# DDR4_Interface.net
KiCad netlist of a schematic drawn in Altium Designer
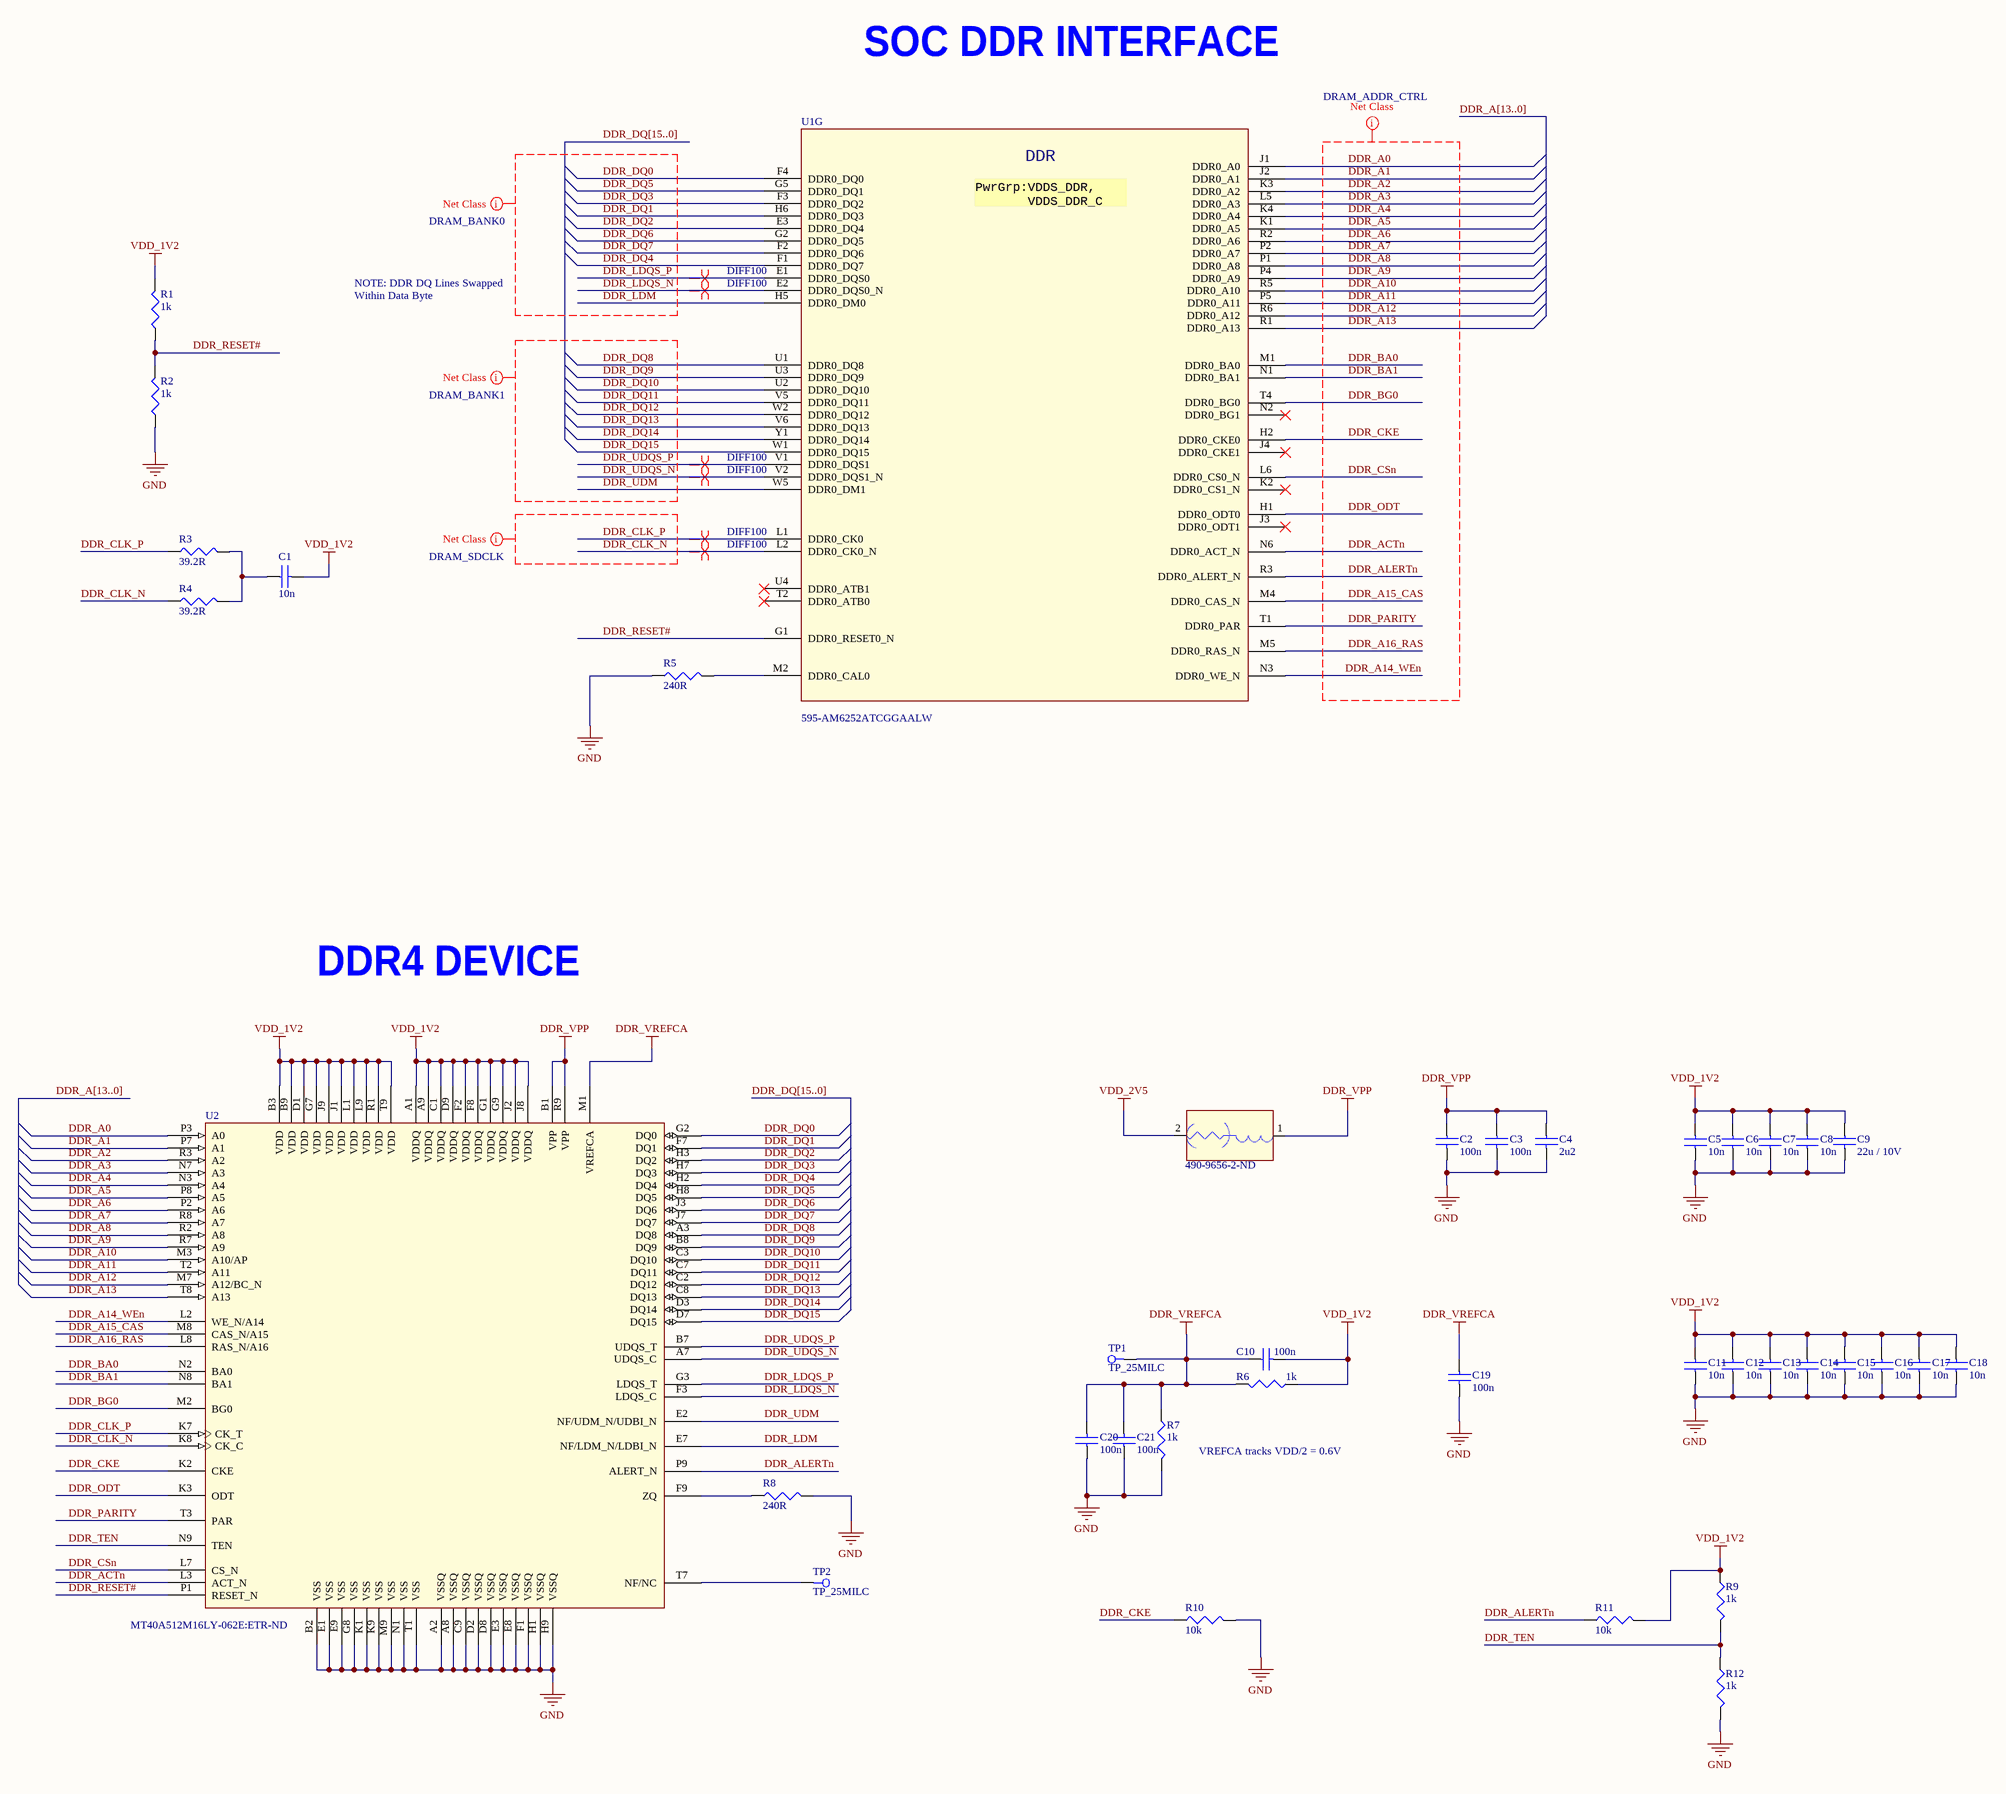
[diagram p0: DDR4 Interface.SchDoc]

(export (version "E")
  (design (tool "Eeschema 10.0.6"))
  (components
    (comp (ref "C1")
      (value "10n")
      (footprint "C0201")
      (description "CAP CER .01UF 16V 10% X5R 0201")
      (fields
        (field (name "MANUFACTURER") "TDK Corporation")
        (field (name "MANUFACTURER PART NUMBER") "C0603X5R1C103K030BA")
        (field (name ".CREATOR") "MM")
        (field (name ".CHECKED PCB") "MM")
        (field (name ".CHECKED SCH") "MM")
      )
      (libsource (lib "Schlib AM625") (part "C0603X5R1C103K030BA"))
    )
    (comp (ref "C2")
      (value "100n")
      (footprint "C0201")
      (description "CAP CER 0.1UF 16V 10% X5R 0201")
      (fields
        (field (name "MANUFACTURER") "TDK Corporation")
        (field (name "MANUFACTURER PART NUMBER") "C0603X5R1C104K030BC")
        (field (name ".CREATOR") "MM")
        (field (name ".CHECKED PCB") "MM")
        (field (name ".CHECKED SCH") "MM")
      )
      (libsource (lib "Schlib AM625") (part "C0603X5R1C104K030BC"))
    )
    (comp (ref "C3")
      (value "100n")
      (footprint "C0201")
      (description "CAP CER 0.1UF 16V 10% X5R 0201")
      (fields
        (field (name "MANUFACTURER") "TDK Corporation")
        (field (name "MANUFACTURER PART NUMBER") "C0603X5R1C104K030BC")
        (field (name ".CREATOR") "MM")
        (field (name ".CHECKED PCB") "MM")
        (field (name ".CHECKED SCH") "MM")
      )
      (libsource (lib "Schlib AM625") (part "C0603X5R1C104K030BC"))
    )
    (comp (ref "C4")
      (value "2u2")
      (footprint "C0402")
      (description "CAP CER 2.2UF 10V 10% X5R 0402")
      (fields
        (field (name "MANUFACTURER") "TDK Corporation")
        (field (name "MANUFACTURER PART NUMBER") "C1005X5R1A225K")
      )
      (libsource (lib "Schlib AM625") (part "C1005X5R1A225K"))
    )
    (comp (ref "C5")
      (value "10n")
      (footprint "C0201")
      (description "CAP CER .01UF 16V 10% X5R 0201")
      (fields
        (field (name "MANUFACTURER") "TDK Corporation")
        (field (name "MANUFACTURER PART NUMBER") "C0603X5R1C103K030BA")
        (field (name ".CREATOR") "MM")
        (field (name ".CHECKED PCB") "MM")
        (field (name ".CHECKED SCH") "MM")
      )
      (libsource (lib "Schlib AM625") (part "C0603X5R1C103K030BA"))
    )
    (comp (ref "C6")
      (value "10n")
      (footprint "C0201")
      (description "CAP CER .01UF 16V 10% X5R 0201")
      (fields
        (field (name "MANUFACTURER") "TDK Corporation")
        (field (name "MANUFACTURER PART NUMBER") "C0603X5R1C103K030BA")
        (field (name ".CREATOR") "MM")
        (field (name ".CHECKED PCB") "MM")
        (field (name ".CHECKED SCH") "MM")
      )
      (libsource (lib "Schlib AM625") (part "C0603X5R1C103K030BA"))
    )
    (comp (ref "C7")
      (value "10n")
      (footprint "C0201")
      (description "CAP CER .01UF 16V 10% X5R 0201")
      (fields
        (field (name "MANUFACTURER") "TDK Corporation")
        (field (name "MANUFACTURER PART NUMBER") "C0603X5R1C103K030BA")
        (field (name ".CREATOR") "MM")
        (field (name ".CHECKED PCB") "MM")
        (field (name ".CHECKED SCH") "MM")
      )
      (libsource (lib "Schlib AM625") (part "C0603X5R1C103K030BA"))
    )
    (comp (ref "C8")
      (value "10n")
      (footprint "C0201")
      (description "CAP CER .01UF 16V 10% X5R 0201")
      (fields
        (field (name "MANUFACTURER") "TDK Corporation")
        (field (name "MANUFACTURER PART NUMBER") "C0603X5R1C103K030BA")
        (field (name ".CREATOR") "MM")
        (field (name ".CHECKED PCB") "MM")
        (field (name ".CHECKED SCH") "MM")
      )
      (libsource (lib "Schlib AM625") (part "C0603X5R1C103K030BA"))
    )
    (comp (ref "C9")
      (value "22u / 10V")
      (footprint "C0603")
      (description "CAP CER 22UF 10V X5R 0603")
      (fields
        (field (name "MANUFACTURER") "TDK Corporation")
        (field (name "MANUFACTURER PART NUMBER") "C1608X5R1A226M080AC")
        (field (name ".CREATOR") "MM")
        (field (name ".CHECKED SCH") "MM")
        (field (name ".CHECKED PCB") "MM")
      )
      (libsource (lib "Schlib AM625") (part "C1608X5R1A226M080AC"))
    )
    (comp (ref "C10")
      (value "100n")
      (footprint "C0201")
      (description "CAP CER 0.1UF 16V 10% X5R 0201")
      (fields
        (field (name "MANUFACTURER") "TDK Corporation")
        (field (name "MANUFACTURER PART NUMBER") "C0603X5R1C104K030BC")
        (field (name ".CREATOR") "MM")
        (field (name ".CHECKED PCB") "MM")
        (field (name ".CHECKED SCH") "MM")
      )
      (libsource (lib "Schlib AM625") (part "C0603X5R1C104K030BC"))
    )
    (comp (ref "C11")
      (value "10n")
      (footprint "C0201")
      (description "CAP CER .01UF 16V 10% X5R 0201")
      (fields
        (field (name "MANUFACTURER") "TDK Corporation")
        (field (name "MANUFACTURER PART NUMBER") "C0603X5R1C103K030BA")
        (field (name ".CREATOR") "MM")
        (field (name ".CHECKED PCB") "MM")
        (field (name ".CHECKED SCH") "MM")
      )
      (libsource (lib "Schlib AM625") (part "C0603X5R1C103K030BA"))
    )
    (comp (ref "C12")
      (value "10n")
      (footprint "C0201")
      (description "CAP CER .01UF 16V 10% X5R 0201")
      (fields
        (field (name "MANUFACTURER") "TDK Corporation")
        (field (name "MANUFACTURER PART NUMBER") "C0603X5R1C103K030BA")
        (field (name ".CREATOR") "MM")
        (field (name ".CHECKED PCB") "MM")
        (field (name ".CHECKED SCH") "MM")
      )
      (libsource (lib "Schlib AM625") (part "C0603X5R1C103K030BA"))
    )
    (comp (ref "C13")
      (value "10n")
      (footprint "C0201")
      (description "CAP CER .01UF 16V 10% X5R 0201")
      (fields
        (field (name "MANUFACTURER") "TDK Corporation")
        (field (name "MANUFACTURER PART NUMBER") "C0603X5R1C103K030BA")
        (field (name ".CREATOR") "MM")
        (field (name ".CHECKED PCB") "MM")
        (field (name ".CHECKED SCH") "MM")
      )
      (libsource (lib "Schlib AM625") (part "C0603X5R1C103K030BA"))
    )
    (comp (ref "C14")
      (value "10n")
      (footprint "C0201")
      (description "CAP CER .01UF 16V 10% X5R 0201")
      (fields
        (field (name "MANUFACTURER") "TDK Corporation")
        (field (name "MANUFACTURER PART NUMBER") "C0603X5R1C103K030BA")
        (field (name ".CREATOR") "MM")
        (field (name ".CHECKED PCB") "MM")
        (field (name ".CHECKED SCH") "MM")
      )
      (libsource (lib "Schlib AM625") (part "C0603X5R1C103K030BA"))
    )
    (comp (ref "C15")
      (value "10n")
      (footprint "C0201")
      (description "CAP CER .01UF 16V 10% X5R 0201")
      (fields
        (field (name "MANUFACTURER") "TDK Corporation")
        (field (name "MANUFACTURER PART NUMBER") "C0603X5R1C103K030BA")
        (field (name ".CREATOR") "MM")
        (field (name ".CHECKED PCB") "MM")
        (field (name ".CHECKED SCH") "MM")
      )
      (libsource (lib "Schlib AM625") (part "C0603X5R1C103K030BA"))
    )
    (comp (ref "C16")
      (value "10n")
      (footprint "C0201")
      (description "CAP CER .01UF 16V 10% X5R 0201")
      (fields
        (field (name "MANUFACTURER") "TDK Corporation")
        (field (name "MANUFACTURER PART NUMBER") "C0603X5R1C103K030BA")
        (field (name ".CREATOR") "MM")
        (field (name ".CHECKED PCB") "MM")
        (field (name ".CHECKED SCH") "MM")
      )
      (libsource (lib "Schlib AM625") (part "C0603X5R1C103K030BA"))
    )
    (comp (ref "C17")
      (value "10n")
      (footprint "C0201")
      (description "CAP CER .01UF 16V 10% X5R 0201")
      (fields
        (field (name "MANUFACTURER") "TDK Corporation")
        (field (name "MANUFACTURER PART NUMBER") "C0603X5R1C103K030BA")
        (field (name ".CREATOR") "MM")
        (field (name ".CHECKED PCB") "MM")
        (field (name ".CHECKED SCH") "MM")
      )
      (libsource (lib "Schlib AM625") (part "C0603X5R1C103K030BA"))
    )
    (comp (ref "C18")
      (value "10n")
      (footprint "C0201")
      (description "CAP CER .01UF 16V 10% X5R 0201")
      (fields
        (field (name "MANUFACTURER") "TDK Corporation")
        (field (name "MANUFACTURER PART NUMBER") "C0603X5R1C103K030BA")
        (field (name ".CREATOR") "MM")
        (field (name ".CHECKED PCB") "MM")
        (field (name ".CHECKED SCH") "MM")
      )
      (libsource (lib "Schlib AM625") (part "C0603X5R1C103K030BA"))
    )
    (comp (ref "C19")
      (value "100n")
      (footprint "C0201")
      (description "CAP CER 0.1UF 16V 10% X5R 0201")
      (fields
        (field (name "MANUFACTURER") "TDK Corporation")
        (field (name "MANUFACTURER PART NUMBER") "C0603X5R1C104K030BC")
        (field (name ".CREATOR") "MM")
        (field (name ".CHECKED PCB") "MM")
        (field (name ".CHECKED SCH") "MM")
      )
      (libsource (lib "Schlib AM625") (part "C0603X5R1C104K030BC"))
    )
    (comp (ref "C20")
      (value "100n")
      (footprint "C0201")
      (description "CAP CER 0.1UF 16V 10% X5R 0201")
      (fields
        (field (name "MANUFACTURER") "TDK Corporation")
        (field (name "MANUFACTURER PART NUMBER") "C0603X5R1C104K030BC")
        (field (name ".CREATOR") "MM")
        (field (name ".CHECKED PCB") "MM")
        (field (name ".CHECKED SCH") "MM")
      )
      (libsource (lib "Schlib AM625") (part "C0603X5R1C104K030BC"))
    )
    (comp (ref "C21")
      (value "100n")
      (footprint "C0201")
      (description "CAP CER 0.1UF 16V 10% X5R 0201")
      (fields
        (field (name "MANUFACTURER") "TDK Corporation")
        (field (name "MANUFACTURER PART NUMBER") "C0603X5R1C104K030BC")
        (field (name ".CREATOR") "MM")
        (field (name ".CHECKED PCB") "MM")
        (field (name ".CHECKED SCH") "MM")
      )
      (libsource (lib "Schlib AM625") (part "C0603X5R1C104K030BC"))
    )
    (comp (ref "FL1")
      (value "BLM15PX121SN1D")
      (footprint "NFZ15SG152SN10B")
      (description "FERRITE BEAD 120 OHM 0402 1LN")
      (fields
        (field (name "MANUFACTURER") "Murata")
        (field (name "TOLERANCE") "25%")
        (field (name "SUPPLIER PART NUMBER 1") "490-9656-2-ND")
      )
      (libsource (lib "Schlib AM625") (part "BLM15PX121SN1D"))
    )
    (comp (ref "R1")
      (value "1k")
      (footprint "R0201")
      (description "RES 1K OHM 1/20W 1% 0201 SMD")
      (fields
        (field (name "MANUFACTURER") "Yageo")
        (field (name "MANUFACTURER PART NUMBER") "RC0201FR-071KL")
        (field (name ".CREATOR") "MM")
        (field (name ".CHECKED PCB") "MM")
        (field (name ".CHECKED SCH") "MM")
      )
      (libsource (lib "Schlib AM625") (part "RC0201FR-071KL"))
    )
    (comp (ref "R2")
      (value "1k")
      (footprint "R0201")
      (description "RES 1K OHM 1/20W 1% 0201 SMD")
      (fields
        (field (name "MANUFACTURER") "Yageo")
        (field (name "MANUFACTURER PART NUMBER") "RC0201FR-071KL")
        (field (name ".CREATOR") "MM")
        (field (name ".CHECKED PCB") "MM")
        (field (name ".CHECKED SCH") "MM")
      )
      (libsource (lib "Schlib AM625") (part "RC0201FR-071KL"))
    )
    (comp (ref "R3")
      (value "39.2R")
      (footprint "R0402")
      (description "RES 39.2 OHM 1% 1/16W 0402")
      (fields
        (field (name "MANUFACTURER") "Stackpole Electronics")
        (field (name "MANUFACTURER PART NUMBER") "RMCF0402FT39R2")
      )
      (libsource (lib "Schlib AM625") (part "RMCF0402FT39R2"))
    )
    (comp (ref "R4")
      (value "39.2R")
      (footprint "R0402")
      (description "RES 39.2 OHM 1% 1/16W 0402")
      (fields
        (field (name "MANUFACTURER") "Stackpole Electronics")
        (field (name "MANUFACTURER PART NUMBER") "RMCF0402FT39R2")
      )
      (libsource (lib "Schlib AM625") (part "RMCF0402FT39R2"))
    )
    (comp (ref "R5")
      (value "240R")
      (footprint "R0201")
      (description "RES 240 OHM 1/20W 1% 0201")
      (fields
        (field (name "MANUFACTURER") "Stackpole Electronics Inc")
        (field (name "MANUFACTURER PART NUMBER") "RMCF0201FT240R")
        (field (name ".CREATOR") "MM")
        (field (name ".CHECKED PCB") "MM")
        (field (name ".CHECKED SCH") "MM")
      )
      (libsource (lib "Schlib AM625") (part "RMCF0201FT240R"))
    )
    (comp (ref "R6")
      (value "1k")
      (footprint "R0201")
      (description "RES 1K OHM 1/20W 1% 0201 SMD")
      (fields
        (field (name "MANUFACTURER") "Yageo")
        (field (name "MANUFACTURER PART NUMBER") "RC0201FR-071KL")
        (field (name ".CREATOR") "MM")
        (field (name ".CHECKED PCB") "MM")
        (field (name ".CHECKED SCH") "MM")
      )
      (libsource (lib "Schlib AM625") (part "RC0201FR-071KL"))
    )
    (comp (ref "R7")
      (value "1k")
      (footprint "R0201")
      (description "RES 1K OHM 1/20W 1% 0201 SMD")
      (fields
        (field (name "MANUFACTURER") "Yageo")
        (field (name "MANUFACTURER PART NUMBER") "RC0201FR-071KL")
        (field (name ".CREATOR") "MM")
        (field (name ".CHECKED PCB") "MM")
        (field (name ".CHECKED SCH") "MM")
      )
      (libsource (lib "Schlib AM625") (part "RC0201FR-071KL"))
    )
    (comp (ref "R8")
      (value "240R")
      (footprint "R0402")
      (description "RES TF 240 OHM 1% 0.0625W 0402")
      (fields
        (field (name "MANUFACTURER") "Stackpole Electronics Inc")
        (field (name "MANUFACTURER PART NUMBER") "RMCF0402FT240R")
      )
      (libsource (lib "Schlib AM625") (part "RMCF0402FT240R"))
    )
    (comp (ref "R9")
      (value "1k")
      (footprint "R0201")
      (description "RES 1K OHM 1/20W 1% 0201 SMD")
      (fields
        (field (name "MANUFACTURER") "Yageo")
        (field (name "MANUFACTURER PART NUMBER") "RC0201FR-071KL")
        (field (name ".CREATOR") "MM")
        (field (name ".CHECKED PCB") "MM")
        (field (name ".CHECKED SCH") "MM")
      )
      (libsource (lib "Schlib AM625") (part "RC0201FR-071KL"))
    )
    (comp (ref "R10")
      (value "10k")
      (footprint "R0201")
      (description "RES 10K OHM 1/20W 1% 0201 SMD")
      (fields
        (field (name "MANUFACTURER") "Yageo")
        (field (name "MANUFACTURER PART NUMBER") "RC0201FR-0710KL")
        (field (name ".CREATOR") "MM")
        (field (name ".CHECKED PCB") "MM")
        (field (name ".CHECKED SCH") "MM")
      )
      (libsource (lib "Schlib AM625") (part "RC0201FR-0710KL"))
    )
    (comp (ref "R11")
      (value "10k")
      (footprint "R0201")
      (description "RES 10K OHM 1/20W 1% 0201 SMD")
      (fields
        (field (name "MANUFACTURER") "Yageo")
        (field (name "MANUFACTURER PART NUMBER") "RC0201FR-0710KL")
        (field (name ".CREATOR") "MM")
        (field (name ".CHECKED PCB") "MM")
        (field (name ".CHECKED SCH") "MM")
      )
      (libsource (lib "Schlib AM625") (part "RC0201FR-0710KL"))
    )
    (comp (ref "R12")
      (value "1k")
      (footprint "R0201")
      (description "RES 1K OHM 1/20W 1% 0201 SMD")
      (fields
        (field (name "MANUFACTURER") "Yageo")
        (field (name "MANUFACTURER PART NUMBER") "RC0201FR-071KL")
        (field (name ".CREATOR") "MM")
        (field (name ".CHECKED PCB") "MM")
        (field (name ".CHECKED SCH") "MM")
      )
      (libsource (lib "Schlib AM625") (part "RC0201FR-071KL"))
    )
    (comp (ref "TP1")
      (value "TP_25MILC")
      (footprint "TP_25C")
      (description "Test Point 25mil")
      (libsource (lib "Schlib AM625") (part "TP_25MILC"))
    )
    (comp (ref "TP2")
      (value "TP_25MILC")
      (footprint "TP_25C")
      (description "Test Point 25mil")
      (libsource (lib "Schlib AM625") (part "TP_25MILC"))
    )
    (comp (ref "U1")
      (value "AM62-EVM_BGA425")
      (footprint "BGA425C50P25X25_1300X1300X89")
      (description "ARM® Cortex®-A53 Microprocessor IC Sitara™ 2 Core, 64-Bit 1.4GHz 425-FCCSP (13x13)")
      (fields
        (field (name "MANUFACTURER") "Texas Instruments")
        (field (name "MANUFACTURER PART NUMBER") "AM6252ATCGGAALW")
        (field (name "SUPPLIER PART NUMBER 1") "595-AM6252ATCGGAALW")
      )
      (libsource (lib "Schlib AM625") (part "AM62-EVM_BGA425"))
    )
    (comp (ref "U2")
      (value "MT40A512M16LY_FBGA96")
      (footprint "BGA96C80P9X16_750X1350X120")
      (description "SDRAM - DDR4 Memory IC 8Gbit Parallel 1.33 GHz 96-FBGA (7.5x13.5)")
      (fields
        (field (name "MANUFACTURER") "Micron Technology")
        (field (name "MANUFACTURER PART NUMBER") "MT40A512M16LY-062E:E TR")
        (field (name "SUPPLIER PART NUMBER 1") "MT40A512M16LY-062E:ETR-ND")
      )
      (libsource (lib "Schlib AM625") (part "MT40A512M16LY_FBGA96"))
    )
  )
  (nets
    (net (code "1") (name "/DDR_A0") (class "Default")
      (node (ref "U1") (pin "J1") (pinfunction "DDR0_A0_J1") (pintype "passive"))
      (node (ref "U2") (pin "P3") (pinfunction "A0_P3") (pintype "input"))
    )
    (net (code "2") (name "/DDR_A1") (class "Default")
      (node (ref "U1") (pin "J2") (pinfunction "DDR0_A1_J2") (pintype "passive"))
      (node (ref "U2") (pin "P7") (pinfunction "A1_P7") (pintype "input"))
    )
    (net (code "3") (name "/DDR_A2") (class "Default")
      (node (ref "U1") (pin "K3") (pinfunction "DDR0_A2_K3") (pintype "passive"))
      (node (ref "U2") (pin "R3") (pinfunction "A2_R3") (pintype "input"))
    )
    (net (code "4") (name "/DDR_A3") (class "Default")
      (node (ref "U1") (pin "L5") (pinfunction "DDR0_A3_L5") (pintype "passive"))
      (node (ref "U2") (pin "N7") (pinfunction "A3_N7") (pintype "input"))
    )
    (net (code "5") (name "/DDR_A4") (class "Default")
      (node (ref "U1") (pin "K4") (pinfunction "DDR0_A4_K4") (pintype "passive"))
      (node (ref "U2") (pin "N3") (pinfunction "A4_N3") (pintype "input"))
    )
    (net (code "6") (name "/DDR_A5") (class "Default")
      (node (ref "U1") (pin "K1") (pinfunction "DDR0_A5_K1") (pintype "passive"))
      (node (ref "U2") (pin "P8") (pinfunction "A5_P8") (pintype "input"))
    )
    (net (code "7") (name "/DDR_A6") (class "Default")
      (node (ref "U1") (pin "R2") (pinfunction "DDR0_A6_R2") (pintype "passive"))
      (node (ref "U2") (pin "P2") (pinfunction "A6_P2") (pintype "input"))
    )
    (net (code "8") (name "/DDR_A7") (class "Default")
      (node (ref "U1") (pin "P2") (pinfunction "DDR0_A7_P2") (pintype "passive"))
      (node (ref "U2") (pin "R8") (pinfunction "A7_R8") (pintype "input"))
    )
    (net (code "9") (name "/DDR_A8") (class "Default")
      (node (ref "U1") (pin "P1") (pinfunction "DDR0_A8_P1") (pintype "passive"))
      (node (ref "U2") (pin "R2") (pinfunction "A8_R2") (pintype "input"))
    )
    (net (code "10") (name "/DDR_A9") (class "Default")
      (node (ref "U1") (pin "P4") (pinfunction "DDR0_A9_P4") (pintype "passive"))
      (node (ref "U2") (pin "R7") (pinfunction "A9_R7") (pintype "input"))
    )
    (net (code "11") (name "/DDR_A10") (class "Default")
      (node (ref "U1") (pin "R5") (pinfunction "DDR0_A10_R5") (pintype "passive"))
      (node (ref "U2") (pin "M3") (pinfunction "A10/AP_M3") (pintype "input"))
    )
    (net (code "12") (name "/DDR_A11") (class "Default")
      (node (ref "U1") (pin "P5") (pinfunction "DDR0_A11_P5") (pintype "passive"))
      (node (ref "U2") (pin "T2") (pinfunction "A11_T2") (pintype "input"))
    )
    (net (code "13") (name "/DDR_A12") (class "Default")
      (node (ref "U1") (pin "R6") (pinfunction "DDR0_A12_R6") (pintype "passive"))
      (node (ref "U2") (pin "M7") (pinfunction "A12/BC_N_M7") (pintype "input"))
    )
    (net (code "14") (name "/DDR_A13") (class "Default")
      (node (ref "U1") (pin "R1") (pinfunction "DDR0_A13_R1") (pintype "passive"))
      (node (ref "U2") (pin "T8") (pinfunction "A13_T8") (pintype "input"))
    )
    (net (code "15") (name "/DDR_A14_WEn") (class "Default")
      (node (ref "U1") (pin "N3") (pinfunction "DDR0_WE_N_N3") (pintype "passive"))
      (node (ref "U2") (pin "L2") (pinfunction "WE_N/A14_L2") (pintype "passive"))
    )
    (net (code "16") (name "/DDR_A15_CAS") (class "Default")
      (node (ref "U1") (pin "M4") (pinfunction "DDR0_CAS_N_M4") (pintype "passive"))
      (node (ref "U2") (pin "M8") (pinfunction "CAS_N/A15_M8") (pintype "passive"))
    )
    (net (code "17") (name "/DDR_A16_RAS") (class "Default")
      (node (ref "U1") (pin "M5") (pinfunction "DDR0_RAS_N_M5") (pintype "passive"))
      (node (ref "U2") (pin "L8") (pinfunction "RAS_N/A16_L8") (pintype "passive"))
    )
    (net (code "18") (name "/DDR_ACTn") (class "Default")
      (node (ref "U1") (pin "N6") (pinfunction "DDR0_ACT_N_N6") (pintype "passive"))
      (node (ref "U2") (pin "L3") (pinfunction "ACT_N_L3") (pintype "passive"))
    )
    (net (code "19") (name "/DDR_ALERTn") (class "Default")
      (node (ref "R11") (pin "1") (pinfunction "1_1") (pintype "passive"))
      (node (ref "U1") (pin "R3") (pinfunction "DDR0_ALERT_N_R3") (pintype "passive"))
      (node (ref "U2") (pin "P9") (pinfunction "ALERT_N_P9") (pintype "passive"))
    )
    (net (code "21") (name "/DDR_BA0") (class "Default")
      (node (ref "U1") (pin "M1") (pinfunction "DDR0_BA0_M1") (pintype "passive"))
      (node (ref "U2") (pin "N2") (pinfunction "BA0_N2") (pintype "passive"))
    )
    (net (code "22") (name "/DDR_BA1") (class "Default")
      (node (ref "U1") (pin "N1") (pinfunction "DDR0_BA1_N1") (pintype "passive"))
      (node (ref "U2") (pin "N8") (pinfunction "BA1_N8") (pintype "passive"))
    )
    (net (code "23") (name "/DDR_BG0") (class "Default")
      (node (ref "U1") (pin "T4") (pinfunction "DDR0_BG0_T4") (pintype "passive"))
      (node (ref "U2") (pin "M2") (pinfunction "BG0_M2") (pintype "passive"))
    )
    (net (code "24") (name "/DDR_CKE") (class "Default")
      (node (ref "R10") (pin "1") (pinfunction "1_1") (pintype "passive"))
      (node (ref "U1") (pin "H2") (pinfunction "DDR0_CKE0_H2") (pintype "passive"))
      (node (ref "U2") (pin "K2") (pinfunction "CKE_K2") (pintype "passive"))
    )
    (net (code "25") (name "/DDR_CLK_N") (class "Default")
      (node (ref "R4") (pin "1") (pinfunction "1_1") (pintype "passive"))
      (node (ref "U1") (pin "L2") (pinfunction "DDR0_CK0_N_L2") (pintype "passive"))
      (node (ref "U2") (pin "K8") (pinfunction "CK_C_K8") (pintype "input"))
    )
    (net (code "26") (name "/DDR_CLK_P") (class "Default")
      (node (ref "R3") (pin "1") (pinfunction "1_1") (pintype "passive"))
      (node (ref "U1") (pin "L1") (pinfunction "DDR0_CK0_L1") (pintype "passive"))
      (node (ref "U2") (pin "K7") (pinfunction "CK_T_K7") (pintype "input"))
    )
    (net (code "27") (name "/DDR_CSn") (class "Default")
      (node (ref "U1") (pin "L6") (pinfunction "DDR0_CS0_N_L6") (pintype "passive"))
      (node (ref "U2") (pin "L7") (pinfunction "CS_N_L7") (pintype "passive"))
    )
    (net (code "28") (name "/DDR_DQ0") (class "Default")
      (node (ref "U1") (pin "F4") (pinfunction "DDR0_DQ0_F4") (pintype "passive"))
      (node (ref "U2") (pin "G2") (pinfunction "DQ0_G2") (pintype "bidirectional"))
    )
    (net (code "29") (name "/DDR_DQ1") (class "Default")
      (node (ref "U1") (pin "H6") (pinfunction "DDR0_DQ3_H6") (pintype "passive"))
      (node (ref "U2") (pin "F7") (pinfunction "DQ1_F7") (pintype "bidirectional"))
    )
    (net (code "30") (name "/DDR_DQ2") (class "Default")
      (node (ref "U1") (pin "E3") (pinfunction "DDR0_DQ4_E3") (pintype "passive"))
      (node (ref "U2") (pin "H3") (pinfunction "DQ2_H3") (pintype "bidirectional"))
    )
    (net (code "31") (name "/DDR_DQ3") (class "Default")
      (node (ref "U1") (pin "F3") (pinfunction "DDR0_DQ2_F3") (pintype "passive"))
      (node (ref "U2") (pin "H7") (pinfunction "DQ3_H7") (pintype "bidirectional"))
    )
    (net (code "32") (name "/DDR_DQ4") (class "Default")
      (node (ref "U1") (pin "F1") (pinfunction "DDR0_DQ7_F1") (pintype "passive"))
      (node (ref "U2") (pin "H2") (pinfunction "DQ4_H2") (pintype "bidirectional"))
    )
    (net (code "33") (name "/DDR_DQ5") (class "Default")
      (node (ref "U1") (pin "G5") (pinfunction "DDR0_DQ1_G5") (pintype "passive"))
      (node (ref "U2") (pin "H8") (pinfunction "DQ5_H8") (pintype "bidirectional"))
    )
    (net (code "34") (name "/DDR_DQ6") (class "Default")
      (node (ref "U1") (pin "G2") (pinfunction "DDR0_DQ5_G2") (pintype "passive"))
      (node (ref "U2") (pin "J3") (pinfunction "DQ6_J3") (pintype "bidirectional"))
    )
    (net (code "35") (name "/DDR_DQ7") (class "Default")
      (node (ref "U1") (pin "F2") (pinfunction "DDR0_DQ6_F2") (pintype "passive"))
      (node (ref "U2") (pin "J7") (pinfunction "DQ7_J7") (pintype "bidirectional"))
    )
    (net (code "36") (name "/DDR_DQ8") (class "Default")
      (node (ref "U1") (pin "U1") (pinfunction "DDR0_DQ8_U1") (pintype "passive"))
      (node (ref "U2") (pin "A3") (pinfunction "DQ8_A3") (pintype "bidirectional"))
    )
    (net (code "37") (name "/DDR_DQ9") (class "Default")
      (node (ref "U1") (pin "U3") (pinfunction "DDR0_DQ9_U3") (pintype "passive"))
      (node (ref "U2") (pin "B8") (pinfunction "DQ9_B8") (pintype "bidirectional"))
    )
    (net (code "38") (name "/DDR_DQ10") (class "Default")
      (node (ref "U1") (pin "U2") (pinfunction "DDR0_DQ10_U2") (pintype "passive"))
      (node (ref "U2") (pin "C3") (pinfunction "DQ10_C3") (pintype "bidirectional"))
    )
    (net (code "39") (name "/DDR_DQ11") (class "Default")
      (node (ref "U1") (pin "V5") (pinfunction "DDR0_DQ11_V5") (pintype "passive"))
      (node (ref "U2") (pin "C7") (pinfunction "DQ11_C7") (pintype "bidirectional"))
    )
    (net (code "40") (name "/DDR_DQ12") (class "Default")
      (node (ref "U1") (pin "W2") (pinfunction "DDR0_DQ12_W2") (pintype "passive"))
      (node (ref "U2") (pin "C2") (pinfunction "DQ12_C2") (pintype "bidirectional"))
    )
    (net (code "41") (name "/DDR_DQ13") (class "Default")
      (node (ref "U1") (pin "V6") (pinfunction "DDR0_DQ13_V6") (pintype "passive"))
      (node (ref "U2") (pin "C8") (pinfunction "DQ13_C8") (pintype "bidirectional"))
    )
    (net (code "42") (name "/DDR_DQ14") (class "Default")
      (node (ref "U1") (pin "Y1") (pinfunction "DDR0_DQ14_Y1") (pintype "passive"))
      (node (ref "U2") (pin "D3") (pinfunction "DQ14_D3") (pintype "bidirectional"))
    )
    (net (code "43") (name "/DDR_DQ15") (class "Default")
      (node (ref "U1") (pin "W1") (pinfunction "DDR0_DQ15_W1") (pintype "passive"))
      (node (ref "U2") (pin "D7") (pinfunction "DQ15_D7") (pintype "bidirectional"))
    )
    (net (code "45") (name "/DDR_LDM") (class "Default")
      (node (ref "U1") (pin "H5") (pinfunction "DDR0_DM0_H5") (pintype "passive"))
      (node (ref "U2") (pin "E7") (pinfunction "NF/LDM_N/LDBI_N_E7") (pintype "passive"))
    )
    (net (code "46") (name "/DDR_LDQS_N") (class "Default")
      (node (ref "U1") (pin "E2") (pinfunction "DDR0_DQS0_N_E2") (pintype "passive"))
      (node (ref "U2") (pin "F3") (pinfunction "LDQS_C_F3") (pintype "passive"))
    )
    (net (code "47") (name "/DDR_LDQS_P") (class "Default")
      (node (ref "U1") (pin "E1") (pinfunction "DDR0_DQS0_E1") (pintype "passive"))
      (node (ref "U2") (pin "G3") (pinfunction "LDQS_T_G3") (pintype "passive"))
    )
    (net (code "48") (name "/DDR_ODT") (class "Default")
      (node (ref "U1") (pin "H1") (pinfunction "DDR0_ODT0_H1") (pintype "passive"))
      (node (ref "U2") (pin "K3") (pinfunction "ODT_K3") (pintype "passive"))
    )
    (net (code "49") (name "/DDR_PARITY") (class "Default")
      (node (ref "U1") (pin "T1") (pinfunction "DDR0_PAR_T1") (pintype "passive"))
      (node (ref "U2") (pin "T3") (pinfunction "PAR_T3") (pintype "passive"))
    )
    (net (code "50") (name "/DDR_RESET#") (class "Default")
      (node (ref "R1") (pin "1") (pinfunction "1_1") (pintype "passive"))
      (node (ref "R2") (pin "2") (pinfunction "2_2") (pintype "passive"))
      (node (ref "U1") (pin "G1") (pinfunction "DDR0_RESET0_N_G1") (pintype "passive"))
      (node (ref "U2") (pin "P1") (pinfunction "RESET_N_P1") (pintype "passive"))
    )
    (net (code "51") (name "/DDR_TEN") (class "Default")
      (node (ref "R12") (pin "1") (pinfunction "1_1") (pintype "passive"))
      (node (ref "R9") (pin "2") (pinfunction "2_2") (pintype "passive"))
      (node (ref "U2") (pin "N9") (pinfunction "TEN_N9") (pintype "passive"))
    )
    (net (code "52") (name "/DDR_UDM") (class "Default")
      (node (ref "U1") (pin "W5") (pinfunction "DDR0_DM1_W5") (pintype "passive"))
      (node (ref "U2") (pin "E2") (pinfunction "NF/UDM_N/UDBI_N_E2") (pintype "passive"))
    )
    (net (code "53") (name "/DDR_UDQS_N") (class "Default")
      (node (ref "U1") (pin "V2") (pinfunction "DDR0_DQS1_N_V2") (pintype "passive"))
      (node (ref "U2") (pin "A7") (pinfunction "UDQS_C_A7") (pintype "passive"))
    )
    (net (code "54") (name "/DDR_UDQS_P") (class "Default")
      (node (ref "U1") (pin "V1") (pinfunction "DDR0_DQS1_V1") (pintype "passive"))
      (node (ref "U2") (pin "B7") (pinfunction "UDQS_T_B7") (pintype "passive"))
    )
    (net (code "55") (name "DDR_VPP") (class "Default")
      (node (ref "C2") (pin "1") (pinfunction "1_1") (pintype "passive"))
      (node (ref "C3") (pin "1") (pinfunction "1_1") (pintype "passive"))
      (node (ref "C4") (pin "1") (pinfunction "1_1") (pintype "passive"))
      (node (ref "FL1") (pin "1") (pinfunction "1_1") (pintype "passive"))
      (node (ref "U2") (pin "B1") (pinfunction "VPP_B1") (pintype "power_in"))
      (node (ref "U2") (pin "R9") (pinfunction "VPP_R9") (pintype "power_in"))
    )
    (net (code "56") (name "DDR_VREFCA") (class "Default")
      (node (ref "C10") (pin "1") (pinfunction "1_1") (pintype "passive"))
      (node (ref "C19") (pin "1") (pinfunction "1_1") (pintype "passive"))
      (node (ref "C20") (pin "2") (pinfunction "2_2") (pintype "passive"))
      (node (ref "C21") (pin "2") (pinfunction "2_2") (pintype "passive"))
      (node (ref "R6") (pin "2") (pinfunction "2_2") (pintype "passive"))
      (node (ref "R7") (pin "1") (pinfunction "1_1") (pintype "passive"))
      (node (ref "TP1") (pin "1") (pinfunction "1_1") (pintype "passive"))
      (node (ref "U2") (pin "M1") (pinfunction "VREFCA_M1") (pintype "power_in"))
    )
    (net (code "57") (name "GND") (class "Default")
      (node (ref "C11") (pin "1") (pinfunction "1_1") (pintype "passive"))
      (node (ref "C12") (pin "1") (pinfunction "1_1") (pintype "passive"))
      (node (ref "C13") (pin "1") (pinfunction "1_1") (pintype "passive"))
      (node (ref "C14") (pin "1") (pinfunction "1_1") (pintype "passive"))
      (node (ref "C15") (pin "1") (pinfunction "1_1") (pintype "passive"))
      (node (ref "C16") (pin "1") (pinfunction "1_1") (pintype "passive"))
      (node (ref "C17") (pin "1") (pinfunction "1_1") (pintype "passive"))
      (node (ref "C18") (pin "1") (pinfunction "1_1") (pintype "passive"))
      (node (ref "C19") (pin "2") (pinfunction "2_2") (pintype "passive"))
      (node (ref "C2") (pin "2") (pinfunction "2_2") (pintype "passive"))
      (node (ref "C20") (pin "1") (pinfunction "1_1") (pintype "passive"))
      (node (ref "C21") (pin "1") (pinfunction "1_1") (pintype "passive"))
      (node (ref "C3") (pin "2") (pinfunction "2_2") (pintype "passive"))
      (node (ref "C4") (pin "2") (pinfunction "2_2") (pintype "passive"))
      (node (ref "C5") (pin "1") (pinfunction "1_1") (pintype "passive"))
      (node (ref "C6") (pin "1") (pinfunction "1_1") (pintype "passive"))
      (node (ref "C7") (pin "1") (pinfunction "1_1") (pintype "passive"))
      (node (ref "C8") (pin "1") (pinfunction "1_1") (pintype "passive"))
      (node (ref "C9") (pin "2") (pinfunction "2_2") (pintype "passive"))
      (node (ref "R10") (pin "2") (pinfunction "2_2") (pintype "passive"))
      (node (ref "R12") (pin "2") (pinfunction "2_2") (pintype "passive"))
      (node (ref "R2") (pin "1") (pinfunction "1_1") (pintype "passive"))
      (node (ref "R5") (pin "1") (pinfunction "1_1") (pintype "passive"))
      (node (ref "R7") (pin "2") (pinfunction "2_2") (pintype "passive"))
      (node (ref "R8") (pin "2") (pinfunction "2_2") (pintype "passive"))
      (node (ref "U2") (pin "A2") (pinfunction "VSSQ_A2") (pintype "power_in"))
      (node (ref "U2") (pin "A8") (pinfunction "VSSQ_A8") (pintype "power_in"))
      (node (ref "U2") (pin "B2") (pinfunction "VSS_B2") (pintype "power_in"))
      (node (ref "U2") (pin "C9") (pinfunction "VSSQ_C9") (pintype "power_in"))
      (node (ref "U2") (pin "D2") (pinfunction "VSSQ_D2") (pintype "power_in"))
      (node (ref "U2") (pin "D8") (pinfunction "VSSQ_D8") (pintype "power_in"))
      (node (ref "U2") (pin "E1") (pinfunction "VSS_E1") (pintype "power_in"))
      (node (ref "U2") (pin "E3") (pinfunction "VSSQ_E3") (pintype "power_in"))
      (node (ref "U2") (pin "E8") (pinfunction "VSSQ_E8") (pintype "power_in"))
      (node (ref "U2") (pin "E9") (pinfunction "VSS_E9") (pintype "power_in"))
      (node (ref "U2") (pin "F1") (pinfunction "VSSQ_F1") (pintype "power_in"))
      (node (ref "U2") (pin "G8") (pinfunction "VSS_G8") (pintype "power_in"))
      (node (ref "U2") (pin "H1") (pinfunction "VSSQ_H1") (pintype "power_in"))
      (node (ref "U2") (pin "H9") (pinfunction "VSSQ_H9") (pintype "power_in"))
      (node (ref "U2") (pin "K1") (pinfunction "VSS_K1") (pintype "power_in"))
      (node (ref "U2") (pin "K9") (pinfunction "VSS_K9") (pintype "power_in"))
      (node (ref "U2") (pin "M9") (pinfunction "VSS_M9") (pintype "power_in"))
      (node (ref "U2") (pin "N1") (pinfunction "VSS_N1") (pintype "power_in"))
      (node (ref "U2") (pin "T1") (pinfunction "VSS_T1") (pintype "power_in"))
    )
    (net (code "58") (name "Net-(C1-Pad1)") (class "Default")
      (node (ref "C1") (pin "1") (pinfunction "1_1") (pintype "passive"))
      (node (ref "R3") (pin "2") (pinfunction "2_2") (pintype "passive"))
      (node (ref "R4") (pin "2") (pinfunction "2_2") (pintype "passive"))
    )
    (net (code "59") (name "Net-(U1G-DDR0_CAL0)") (class "Default")
      (node (ref "R5") (pin "2") (pinfunction "2_2") (pintype "passive"))
      (node (ref "U1") (pin "M2") (pinfunction "DDR0_CAL0_M2") (pintype "passive"))
    )
    (net (code "60") (name "Net-(U2-NF{slash}NC)") (class "Default")
      (node (ref "TP2") (pin "1") (pinfunction "1_1") (pintype "passive"))
      (node (ref "U2") (pin "T7") (pinfunction "NF/NC_T7") (pintype "passive"))
    )
    (net (code "61") (name "Net-(U2-ZQ)") (class "Default")
      (node (ref "R8") (pin "1") (pinfunction "1_1") (pintype "passive"))
      (node (ref "U2") (pin "F9") (pinfunction "ZQ_F9") (pintype "passive"))
    )
    (net (code "62") (name "VDD_1V2") (class "Default")
      (node (ref "C1") (pin "2") (pinfunction "2_2") (pintype "passive"))
      (node (ref "C10") (pin "2") (pinfunction "2_2") (pintype "passive"))
      (node (ref "C11") (pin "2") (pinfunction "2_2") (pintype "passive"))
      (node (ref "C12") (pin "2") (pinfunction "2_2") (pintype "passive"))
      (node (ref "C13") (pin "2") (pinfunction "2_2") (pintype "passive"))
      (node (ref "C14") (pin "2") (pinfunction "2_2") (pintype "passive"))
      (node (ref "C15") (pin "2") (pinfunction "2_2") (pintype "passive"))
      (node (ref "C16") (pin "2") (pinfunction "2_2") (pintype "passive"))
      (node (ref "C17") (pin "2") (pinfunction "2_2") (pintype "passive"))
      (node (ref "C18") (pin "2") (pinfunction "2_2") (pintype "passive"))
      (node (ref "C5") (pin "2") (pinfunction "2_2") (pintype "passive"))
      (node (ref "C6") (pin "2") (pinfunction "2_2") (pintype "passive"))
      (node (ref "C7") (pin "2") (pinfunction "2_2") (pintype "passive"))
      (node (ref "C8") (pin "2") (pinfunction "2_2") (pintype "passive"))
      (node (ref "C9") (pin "1") (pinfunction "1_1") (pintype "passive"))
      (node (ref "R1") (pin "2") (pinfunction "2_2") (pintype "passive"))
      (node (ref "R11") (pin "2") (pinfunction "2_2") (pintype "passive"))
      (node (ref "R6") (pin "1") (pinfunction "1_1") (pintype "passive"))
      (node (ref "R9") (pin "1") (pinfunction "1_1") (pintype "passive"))
      (node (ref "U2") (pin "A1") (pinfunction "VDDQ_A1") (pintype "power_in"))
      (node (ref "U2") (pin "A9") (pinfunction "VDDQ_A9") (pintype "power_in"))
      (node (ref "U2") (pin "B3") (pinfunction "VDD_B3") (pintype "power_in"))
      (node (ref "U2") (pin "B9") (pinfunction "VDD_B9") (pintype "power_in"))
      (node (ref "U2") (pin "C1") (pinfunction "VDDQ_C1") (pintype "power_in"))
      (node (ref "U2") (pin "D1") (pinfunction "VDD_D1") (pintype "power_in"))
      (node (ref "U2") (pin "D9") (pinfunction "VDDQ_D9") (pintype "power_in"))
      (node (ref "U2") (pin "F2") (pinfunction "VDDQ_F2") (pintype "power_in"))
      (node (ref "U2") (pin "F8") (pinfunction "VDDQ_F8") (pintype "power_in"))
      (node (ref "U2") (pin "G1") (pinfunction "VDDQ_G1") (pintype "power_in"))
      (node (ref "U2") (pin "G7") (pinfunction "VDD_G7") (pintype "power_in"))
      (node (ref "U2") (pin "G9") (pinfunction "VDDQ_G9") (pintype "power_in"))
      (node (ref "U2") (pin "J1") (pinfunction "VDD_J1") (pintype "power_in"))
      (node (ref "U2") (pin "J2") (pinfunction "VDDQ_J2") (pintype "power_in"))
      (node (ref "U2") (pin "J8") (pinfunction "VDDQ_J8") (pintype "power_in"))
      (node (ref "U2") (pin "J9") (pinfunction "VDD_J9") (pintype "power_in"))
      (node (ref "U2") (pin "L1") (pinfunction "VDD_L1") (pintype "power_in"))
      (node (ref "U2") (pin "L9") (pinfunction "VDD_L9") (pintype "power_in"))
      (node (ref "U2") (pin "R1") (pinfunction "VDD_R1") (pintype "power_in"))
      (node (ref "U2") (pin "T9") (pinfunction "VDD_T9") (pintype "power_in"))
    )
    (net (code "63") (name "VDD_2V5") (class "Default")
      (node (ref "FL1") (pin "2") (pinfunction "2_2") (pintype "passive"))
    )
    (net (code "64") (name "unconnected-(U1G-DDR0_ATB0-PadT2)") (class "Default")
      (node (ref "U1") (pin "T2") (pinfunction "DDR0_ATB0_T2") (pintype "passive+no_connect"))
    )
    (net (code "65") (name "unconnected-(U1G-DDR0_ATB1-PadU4)") (class "Default")
      (node (ref "U1") (pin "U4") (pinfunction "DDR0_ATB1_U4") (pintype "passive+no_connect"))
    )
    (net (code "66") (name "unconnected-(U1G-DDR0_BG1-PadN2)") (class "Default")
      (node (ref "U1") (pin "N2") (pinfunction "DDR0_BG1_N2") (pintype "passive+no_connect"))
    )
    (net (code "67") (name "unconnected-(U1G-DDR0_CKE1-PadJ4)") (class "Default")
      (node (ref "U1") (pin "J4") (pinfunction "DDR0_CKE1_J4") (pintype "passive+no_connect"))
    )
    (net (code "68") (name "unconnected-(U1G-DDR0_CS1_N-PadK2)") (class "Default")
      (node (ref "U1") (pin "K2") (pinfunction "DDR0_CS1_N_K2") (pintype "passive+no_connect"))
    )
    (net (code "69") (name "unconnected-(U1G-DDR0_ODT1-PadJ3)") (class "Default")
      (node (ref "U1") (pin "J3") (pinfunction "DDR0_ODT1_J3") (pintype "passive+no_connect"))
    )
  )
)
